# HumidityFan.net
KiCad netlist of a schematic drawn in EAGLE
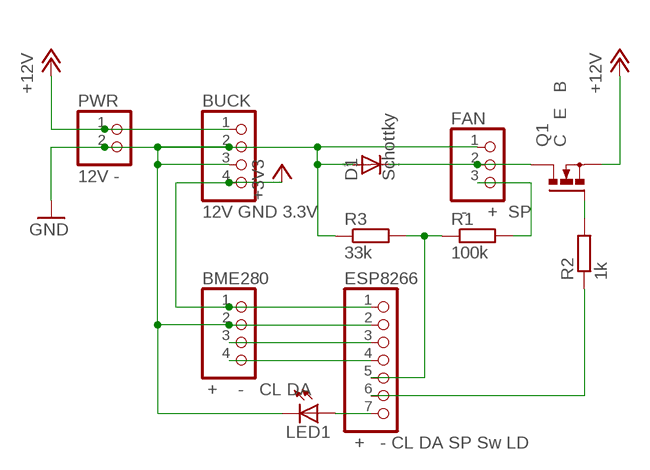
[diagram p0: schematic, sheet 1]

(export (version "E")
  (design (tool "Eeschema 10.0.6"))
  (components
    (comp (ref "BME280")
      (value "+ - CL DA")
      (footprint "eagle-import:1X04")
      (libsource (lib "eagle-import") (part "PINHD-1X4"))
    )
    (comp (ref "BUCK")
      (value "12V GND 3.3V")
      (footprint "eagle-import:1X04")
      (libsource (lib "eagle-import") (part "PINHD-1X4"))
    )
    (comp (ref "D1")
      (value "Schottky")
      (footprint "eagle-import:DO35-10")
      (libsource (lib "eagle-import") (part "1N4446"))
    )
    (comp (ref "ESP8266")
      (value "+ - CL DA SP Sw LD")
      (footprint "eagle-import:1X07")
      (libsource (lib "eagle-import") (part "PINHD-1X7"))
    )
    (comp (ref "FAN")
      (value "- + SP")
      (footprint "eagle-import:1X03")
      (libsource (lib "eagle-import") (part "PINHD-1X3"))
    )
    (comp (ref "LED1")
      (value "LED5MM")
      (footprint "eagle-import:LED5MM")
      (libsource (lib "eagle-import") (part "LED5MM"))
    )
    (comp (ref "PWR")
      (value "12V -")
      (footprint "eagle-import:1X02")
      (libsource (lib "eagle-import") (part "PINHD-1X2"))
    )
    (comp (ref "Q1")
      (value "C E B")
      (footprint "eagle-import:TO220BV")
      (libsource (lib "eagle-import") (part "PMOSFET_NTO220BV"))
    )
    (comp (ref "R1")
      (value "100k")
      (footprint "eagle-import:0204_7")
      (libsource (lib "eagle-import") (part "R-EU_0204/7"))
    )
    (comp (ref "R2")
      (value "1k")
      (footprint "eagle-import:0204_7")
      (libsource (lib "eagle-import") (part "R-EU_0204/7"))
    )
    (comp (ref "R3")
      (value "33k")
      (footprint "eagle-import:0204_7")
      (libsource (lib "eagle-import") (part "R-EU_0204/7"))
    )
  )
  (nets
    (net (code "1") (name "+3V3") (class "Default")
      (node (ref "BME280") (pin "1") (pinfunction "1_1") (pintype "passive"))
      (node (ref "BUCK") (pin "4") (pinfunction "4_4") (pintype "passive"))
      (node (ref "ESP8266") (pin "1") (pinfunction "1_1") (pintype "passive"))
    )
    (net (code "2") (name "+12V") (class "Default")
      (node (ref "BUCK") (pin "1") (pinfunction "1_1") (pintype "passive"))
      (node (ref "PWR") (pin "1") (pinfunction "1_1") (pintype "passive"))
      (node (ref "Q1") (pin "S") (pinfunction "S_S") (pintype "passive"))
    )
    (net (code "3") (name "GND") (class "Default")
      (node (ref "BME280") (pin "2") (pinfunction "2_2") (pintype "passive"))
      (node (ref "BUCK") (pin "2") (pinfunction "2_2") (pintype "passive"))
      (node (ref "BUCK") (pin "3") (pinfunction "3_3") (pintype "passive"))
      (node (ref "D1") (pin "A") (pinfunction "A_A") (pintype "passive"))
      (node (ref "ESP8266") (pin "2") (pinfunction "2_2") (pintype "passive"))
      (node (ref "FAN") (pin "1") (pinfunction "1_1") (pintype "passive"))
      (node (ref "LED1") (pin "K") (pinfunction "C_K") (pintype "passive"))
      (node (ref "PWR") (pin "2") (pinfunction "2_2") (pintype "passive"))
      (node (ref "R3") (pin "1") (pinfunction "1_1") (pintype "passive"))
    )
    (net (code "4") (name "Net-(BME280-Pad3)") (class "Default")
      (node (ref "BME280") (pin "3") (pinfunction "3_3") (pintype "passive"))
      (node (ref "ESP8266") (pin "3") (pinfunction "3_3") (pintype "passive"))
    )
    (net (code "5") (name "Net-(BME280-Pad4)") (class "Default")
      (node (ref "BME280") (pin "4") (pinfunction "4_4") (pintype "passive"))
      (node (ref "ESP8266") (pin "4") (pinfunction "4_4") (pintype "passive"))
    )
    (net (code "6") (name "Net-(D1-PadC)") (class "Default")
      (node (ref "D1") (pin "C") (pinfunction "C_C") (pintype "passive"))
      (node (ref "FAN") (pin "2") (pinfunction "2_2") (pintype "passive"))
      (node (ref "Q1") (pin "D") (pinfunction "D_D") (pintype "passive"))
    )
    (net (code "7") (name "Net-(ESP8266-Pad5)") (class "Default")
      (node (ref "ESP8266") (pin "5") (pinfunction "5_5") (pintype "passive"))
      (node (ref "R1") (pin "1") (pinfunction "1_1") (pintype "passive"))
      (node (ref "R3") (pin "2") (pinfunction "2_2") (pintype "passive"))
    )
    (net (code "8") (name "Net-(ESP8266-Pad6)") (class "Default")
      (node (ref "ESP8266") (pin "6") (pinfunction "6_6") (pintype "passive"))
      (node (ref "R2") (pin "1") (pinfunction "1_1") (pintype "passive"))
    )
    (net (code "9") (name "Net-(ESP8266-Pad7)") (class "Default")
      (node (ref "ESP8266") (pin "7") (pinfunction "7_7") (pintype "passive"))
      (node (ref "LED1") (pin "A") (pinfunction "A_A") (pintype "passive"))
    )
    (net (code "10") (name "Net-(FAN-Pad3)") (class "Default")
      (node (ref "FAN") (pin "3") (pinfunction "3_3") (pintype "passive"))
      (node (ref "R1") (pin "2") (pinfunction "2_2") (pintype "passive"))
    )
    (net (code "11") (name "Net-(Q1-PadG)") (class "Default")
      (node (ref "Q1") (pin "G") (pinfunction "G_G") (pintype "passive"))
      (node (ref "R2") (pin "2") (pinfunction "2_2") (pintype "passive"))
    )
  )
)
